# TOP_MOS_HF.net
KiCad netlist of a schematic drawn in Altium Designer
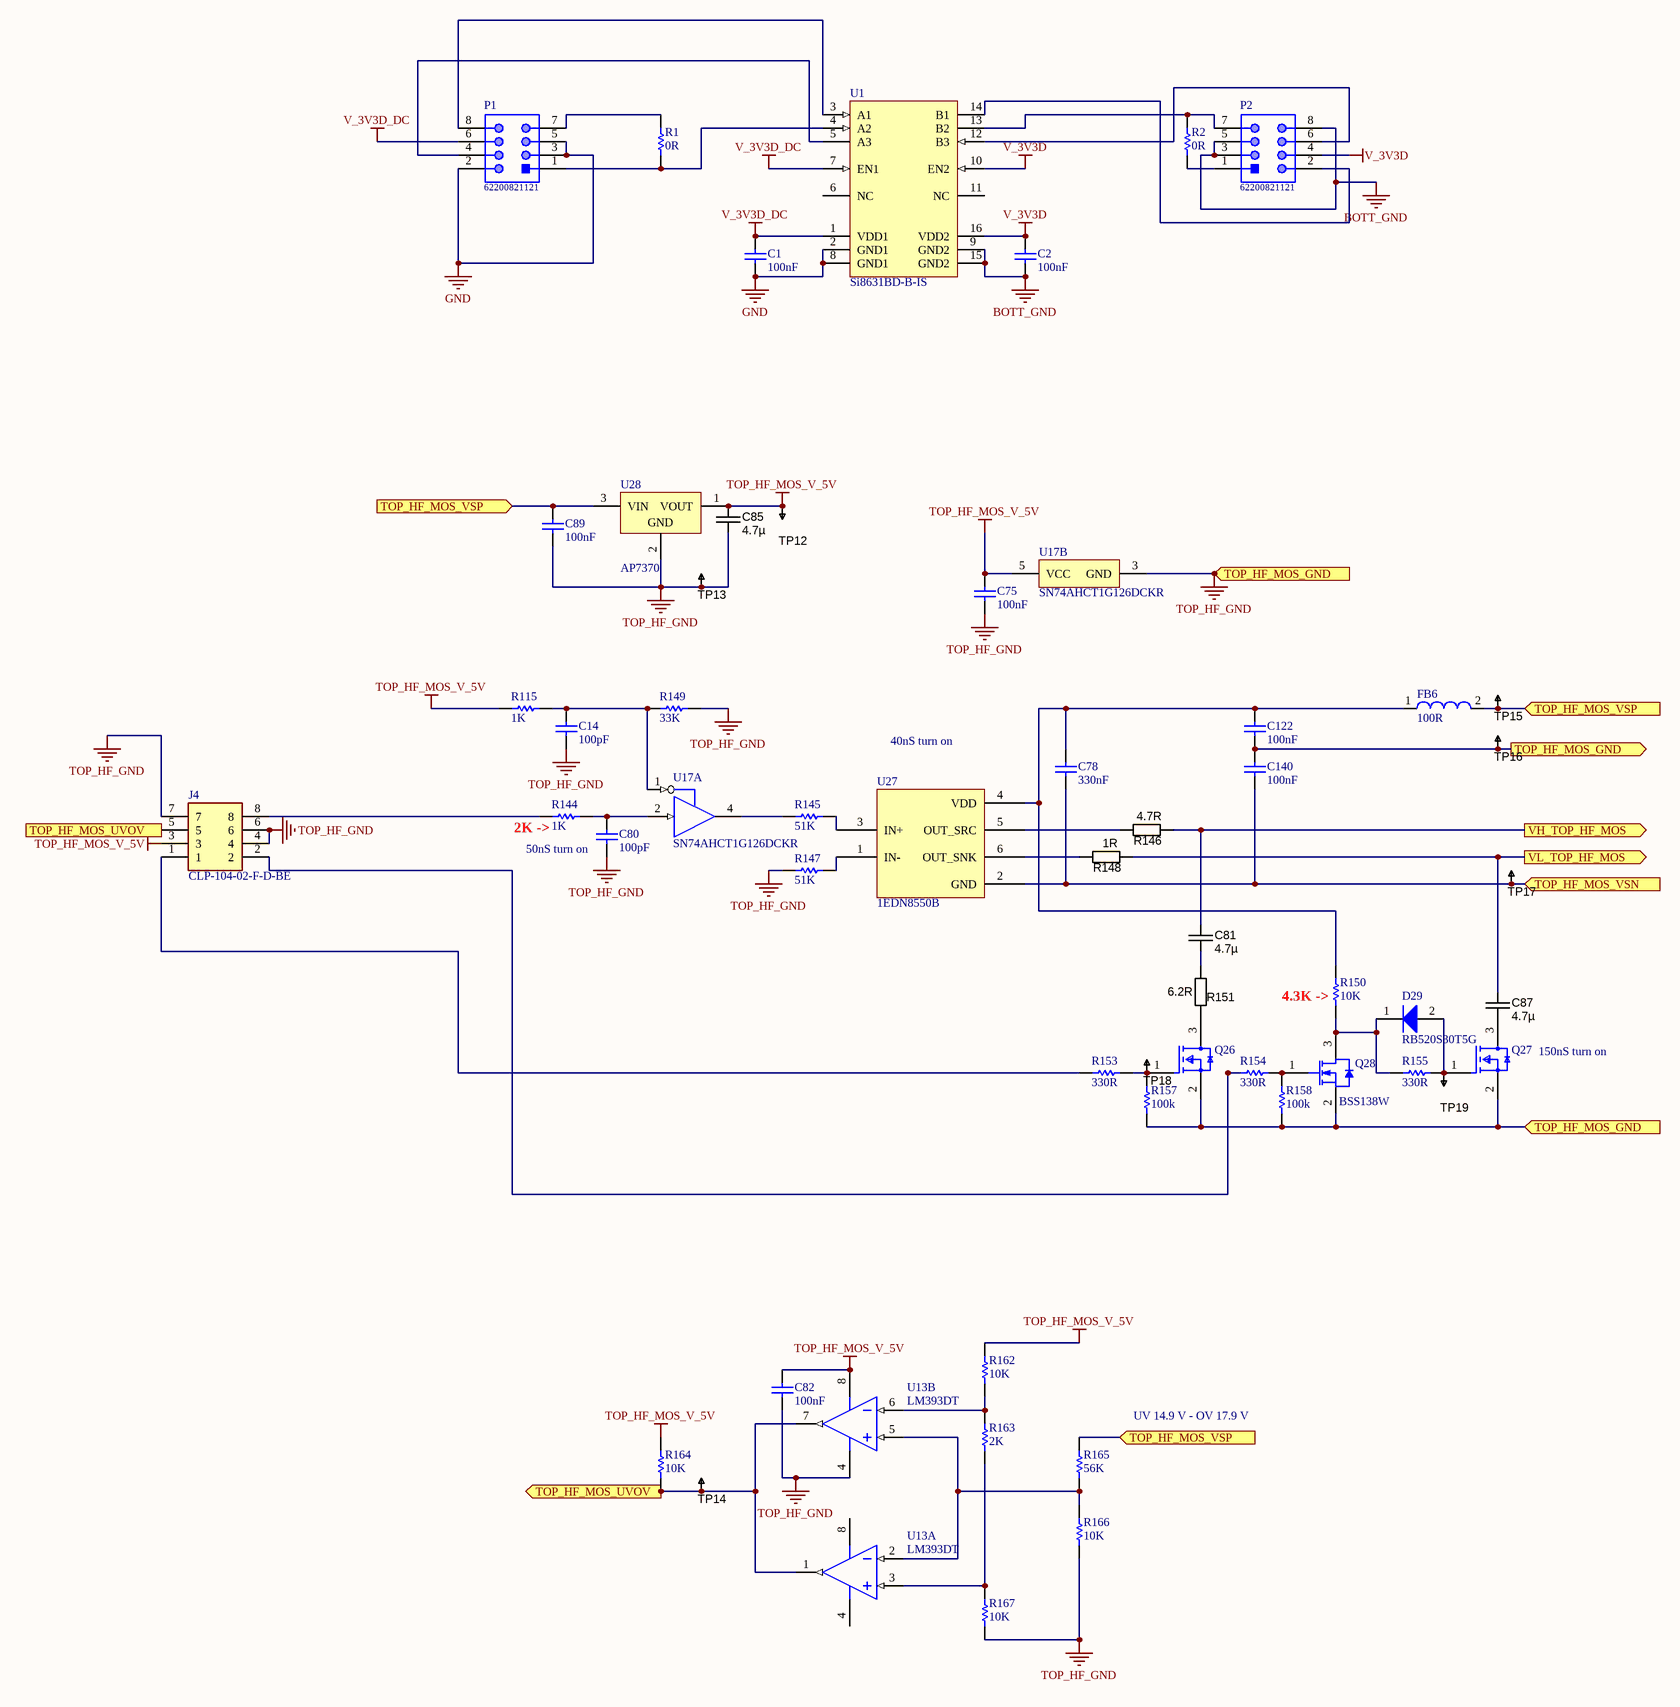
[diagram p0: TOP_MOS_HF.SchDoc]

(export (version "E")
  (design (tool "Eeschema 10.0.6"))
  (components
    (comp (ref "C1")
      (value "100nF")
      (footprint "SAMS-C0603-2_N")
      (description "Cap Ceramic 0.1uF 50VDC X7R 10% SMD 0603 Paper T/R")
      (fields
        (field (name "MANUFACTURER") "Samsung Electro-Mechanics")
        (field (name "MANUFACTURER PART NUMBER") "CL10B104KB8NNNC")
      )
      (libsource (lib "Altium Content Vault") (part "CAP-NP-2"))
    )
    (comp (ref "C2")
      (value "100nF")
      (footprint "SAMS-C0603-2_N")
      (description "Cap Ceramic 0.1uF 50VDC X7R 10% SMD 0603 Paper T/R")
      (fields
        (field (name "MANUFACTURER") "Samsung Electro-Mechanics")
        (field (name "MANUFACTURER PART NUMBER") "CL10B104KB8NNNC")
      )
      (libsource (lib "Altium Content Vault") (part "CAP-NP-2"))
    )
    (comp (ref "C14")
      (value "100pF")
      (footprint "CAPC1005X55X25NL05T10")
      (description "C0G ±5% 50V 100pF 0402 Multilayer Ceramic Capacitors MLCC - SMD/SMT ROHS")
      (fields (field (name "PART NUMBER") "GRM1555C1H100JA01D") (field (name "MANUFACTURER") "Murata"))
      (libsource (lib "DCDC") (part "CMP-2008-04245-1"))
    )
    (comp (ref "C75")
      (value "100nF")
      (footprint "CAPC1608X90X35NL10T15")
      (description "X7R 100nF ±10% 50V 0603 Multilayer Ceramic Capacitors MLCC - SMD/SMT ROHS")
      (fields (field (name "PART NUMBER") "GCM188R72A104KA64D") (field (name "MANUFACTURER") "Murata"))
      (libsource (lib "DCDC") (part "CAP"))
    )
    (comp (ref "C78")
      (value "330nF")
      (footprint "CAPC2013X135X45NL10T25")
      (description "X7R ±10% 50V 330nF 0805 Multilayer Ceramic Capacitors MLCC - SMD/SMT ROHS")
      (fields (field (name "VOLTAGE") "50V") (field (name "TOLERANCE") "10%"))
      (libsource (lib "Altium Content Vault") (part "CAP-NP-2"))
    )
    (comp (ref "C80")
      (value "100pF")
      (footprint "CAPC1005X55X25NL05T10")
      (description "C0G ±5% 50V 100pF 0402 Multilayer Ceramic Capacitors MLCC - SMD/SMT ROHS")
      (fields (field (name "PART NUMBER") "GRM1555C1H100JA01D") (field (name "MANUFACTURER") "Murata"))
      (libsource (lib "DCDC") (part "CMP-2008-04245-1"))
    )
    (comp (ref "C81")
      (value "4.7µ")
      (footprint "CAPC2012X135N")
      (description "X5R 25V ±10% 4.7uF 0805 Multilayer Ceramic Capacitors MLCC - SMD/SMT ROHS")
      (fields (field (name "TOLERANCE") "±10%") (field (name "JLCPCB PART #") "C1779"))
      (libsource (lib "PBL - Capacitors") (part "CAPC_1u_0805_X7R_16V_10%"))
    )
    (comp (ref "C82")
      (value "100nF")
      (footprint "CAPC1608X90X35NL10T15")
      (description "X7R 100nF ±10% 50V 0603 Multilayer Ceramic Capacitors MLCC - SMD/SMT ROHS")
      (fields (field (name "PART NUMBER") "GCM188R72A104KA64D") (field (name "MANUFACTURER") "Murata"))
      (libsource (lib "DCDC") (part "CAP"))
    )
    (comp (ref "C85")
      (value "4.7µ")
      (footprint "CAPC2012X135N")
      (description "X5R 25V ±10% 4.7uF 0805 Multilayer Ceramic Capacitors MLCC - SMD/SMT ROHS")
      (fields (field (name "TOLERANCE") "±10%") (field (name "JLCPCB PART #") "C1779"))
      (libsource (lib "PBL - Capacitors") (part "CAPC_1u_0805_X7R_16V_10%"))
    )
    (comp (ref "C87")
      (value "4.7µ")
      (footprint "CAPC2012X135N")
      (description "X5R 25V ±10% 4.7uF 0805 Multilayer Ceramic Capacitors MLCC - SMD/SMT ROHS")
      (fields (field (name "TOLERANCE") "±10%") (field (name "JLCPCB PART #") "C1779"))
      (libsource (lib "PBL - Capacitors") (part "CAPC_1u_0805_X7R_16V_10%"))
    )
    (comp (ref "C89")
      (value "100nF")
      (footprint "CAPC1608X90X35NL10T15")
      (description "X7R 100nF ±10% 50V 0603 Multilayer Ceramic Capacitors MLCC - SMD/SMT ROHS")
      (fields (field (name "PART NUMBER") "GCM188R72A104KA64D") (field (name "MANUFACTURER") "Murata"))
      (libsource (lib "DCDC") (part "CAP"))
    )
    (comp (ref "C122")
      (value "100nF")
      (footprint "CAPC1608X90X35NL10T15")
      (description "X7R 100nF ±10% 50V 0603 Multilayer Ceramic Capacitors MLCC - SMD/SMT ROHS")
      (fields (field (name "PART NUMBER") "GCM188R72A104KA64D") (field (name "MANUFACTURER") "Murata"))
      (libsource (lib "DCDC") (part "CAP"))
    )
    (comp (ref "C140")
      (value "100nF")
      (footprint "CAPC1608X90X35NL10T15")
      (description "X7R 100nF ±10% 50V 0603 Multilayer Ceramic Capacitors MLCC - SMD/SMT ROHS")
      (fields (field (name "PART NUMBER") "GCM188R72A104KA64D") (field (name "MANUFACTURER") "Murata"))
      (libsource (lib "DCDC") (part "CAP"))
    )
    (comp (ref "D29")
      (value "RB520S30T5G")
      (footprint "ONSC-SOD-523-2-502-01_V")
      (description "Schottky Barrier Diode, 2-Pin SOD-523, Pb-Free, Tape and Reel")
      (fields (field (name "MANUFACTURER") "On Semiconductor"))
      (libsource (lib "Altium Content Vault") (part "ONSC-D-K1A2-2"))
    )
    (comp (ref "FB6")
      (value "100R")
      (footprint "SMD-0603")
      (description "SMD EMI Suppression Ferrite Bead WE-CBF, Z = 1500 Ohm")
      (libsource (lib "Altium Content Vault") (part "PAS-IND-INDUCTOR-2"))
    )
    (comp (ref "J4")
      (value "CLP-104-02-F-D-BE")
      (footprint "SamacSys:CLP-104-02-XXX-D-BE")
      (description "Connector")
      (fields (field (name "MOUSER PART NUMBER") "200-CLP10402FDBE"))
      (libsource (lib "*") (part "CLP-104-02-F-D-BE"))
    )
    (comp (ref "P1")
      (value "62200821121")
      (footprint "EDGE GOLDPIN 8P 1.27MM")
      (description "THT Vertical Pin Header WR-PHD, Pitch 1.27 mm, Dual Row, 8 pins")
      (fields (field (name "MANUFACTURER") "Wurth Elektronik") (field (name "PUBLISHER") "WurthElektronik"))
      (libsource (lib "") (part "WE-CN-2P-M-R8_1"))
    )
    (comp (ref "P2")
      (value "62200821121")
      (footprint "EDGE GOLDPIN 8P 1.27MM")
      (description "THT Vertical Pin Header WR-PHD, Pitch 1.27 mm, Dual Row, 8 pins")
      (fields (field (name "MANUFACTURER") "Wurth Elektronik") (field (name "PUBLISHER") "WurthElektronik"))
      (libsource (lib "SamacSys") (part "WE-CN-2P-M-R8"))
    )
    (comp (ref "Q26")
      (value "DMN3067LW-7")
      (footprint "FP-SOT323-IPC_C")
      (description "MOSFET N-CH 60V 115MA SOT323")
      (libsource (lib "Altium Content Vault") (part "381a366367e4312d0f7d2747150cb42"))
    )
    (comp (ref "Q27")
      (value "DMN3067LW-7")
      (footprint "FP-SOT323-IPC_C")
      (description "MOSFET N-CH 60V 115MA SOT323")
      (libsource (lib "Altium Content Vault") (part "381a366367e4312d0f7d2747150cb42"))
    )
    (comp (ref "Q28")
      (value "BSS138W")
      (footprint "NXP-SOT323_M")
      (description "N-Channel Trench MOSFET, 60 V, 0.32 A, -55 to 150 degC, 3-Pin SOT323, Tape and Reel")
      (fields (field (name "PARTNUMBER") "BSS138PW,115") (field (name "MANUFACTURER") "NXP Semiconductors"))
      (libsource (lib "Altium Content Vault") (part "NXP-NMOS-GSD-3_B"))
    )
    (comp (ref "R1")
      (value "0R")
      (footprint "RESC1608X55X25ML10T15")
      (description "Chip Resistor, 0 Ohm, +/- 5%, 0.1 W, -55 to 155 degC, 0603 (1608 Metric), RoHS, Tape and Reel")
      (fields (field (name "TOLERANCE") "5%") (field (name "MANUFACTURER") "Yageo"))
      (libsource (lib "Altium Content Vault") (part "RES-2"))
    )
    (comp (ref "R2")
      (value "0R")
      (footprint "RESC1608X55X25ML10T15")
      (description "Chip Resistor, 0 Ohm, +/- 5%, 0.1 W, -55 to 155 degC, 0603 (1608 Metric), RoHS, Tape and Reel")
      (fields (field (name "TOLERANCE") "5%") (field (name "MANUFACTURER") "Yageo"))
      (libsource (lib "Altium Content Vault") (part "RES-2"))
    )
    (comp (ref "R115")
      (value "1K")
      (footprint "RESC1005X40X25NL05T10")
      (description "±1% 1/16W ±100ppm/℃ 1kΩ 0402 Chip Resistor - Surface Mount ROHS")
      (fields (field (name "PART NUMBER") "RC0402FR-071KL") (field (name "MANUFACTURER") "Yageo / Phycomp"))
      (libsource (lib "DCDC") (part "CMP-2002-07472-1"))
    )
    (comp (ref "R144")
      (value "1K")
      (footprint "RESC1005X40X25NL05T10")
      (description "±1% 1/16W ±100ppm/℃ 1kΩ 0402 Chip Resistor - Surface Mount ROHS")
      (fields (field (name "PART NUMBER") "RC0402FR-071KL") (field (name "MANUFACTURER") "Yageo / Phycomp"))
      (libsource (lib "DCDC") (part "CMP-2002-07472-1"))
    )
    (comp (ref "R145")
      (value "51K")
      (footprint "RESC1005X40X25ML05T05")
      (fields
        (field (name "PART NUMBER") "ERJ2RKF3302X")
        (field (name "MANUFACTURER") "Panasonic")
        (field (name "MANUFACTURER PART NUMBER") "ERJ-2RKF3302X")
      )
      (libsource (lib "Altium Content Vault") (part "RES"))
    )
    (comp (ref "R146")
      (value "4.7R")
      (footprint "RESC2012X70N")
      (description "4.7Ω ±1% ±400ppm/℃ 0.125W 0805 Chip Resistor - Surface Mount ROHS")
      (fields (field (name "JLCPCB PART #") "C17675"))
      (libsource (lib "PBL - Resistors") (part "RES_EMPTY_0805"))
    )
    (comp (ref "R147")
      (value "51K")
      (footprint "RESC1005X40X25ML05T05")
      (fields
        (field (name "PART NUMBER") "ERJ2RKF3302X")
        (field (name "MANUFACTURER") "Panasonic")
        (field (name "MANUFACTURER PART NUMBER") "ERJ-2RKF3302X")
      )
      (libsource (lib "Altium Content Vault") (part "RES"))
    )
    (comp (ref "R148")
      (value "1R")
      (footprint "RESC2012X70N")
      (description "±1% 1Ω ±400ppm/℃ 0.125W 0805 Chip Resistor - Surface Mount ROHS")
      (fields (field (name "JLCPCB PART #") "C25271"))
      (libsource (lib "PBL - Resistors") (part "RES_EMPTY_0805"))
    )
    (comp (ref "R149")
      (value "33K")
      (footprint "RESC1005X40X25ML05T05")
      (fields
        (field (name "PART NUMBER") "ERJ2RKF3302X")
        (field (name "MANUFACTURER") "Panasonic")
        (field (name "MANUFACTURER PART NUMBER") "ERJ-2RKF3302X")
      )
      (libsource (lib "DCDC") (part "RES"))
    )
    (comp (ref "R150")
      (value "10K")
      (footprint "RESC1609X55X30NL15T15")
      (description "±1% ±100ppm/℃ 10kΩ 0.1W 0603 Chip Resistor - Surface Mount ROHS")
      (fields (field (name "TOLERANCE") "1%") (field (name "MANUFACTURER") "Panasonic"))
      (libsource (lib "Altium Content Vault") (part "RES-2"))
    )
    (comp (ref "R151")
      (value "6.2R")
      (footprint "RESC2012X70N")
      (description "Resistor, 0805 SMD, Empty footprint")
      (libsource (lib "") (part "RES_EMPTY_0805_1"))
    )
    (comp (ref "R153")
      (value "330R")
      (footprint "RESC1608X55X25NL10T15")
      (description "±1% 330Ω ±100ppm/℃ 0.1W 0603 Chip Resistor - Surface Mount ROHS")
      (fields (field (name "TOLERANCE") "10%") (field (name "JLCPCB PART #") "C23138"))
      (libsource (lib "Altium Content Vault") (part "RES-2"))
    )
    (comp (ref "R154")
      (value "330R")
      (footprint "RESC1608X55X25NL10T15")
      (description "±1% 330Ω ±100ppm/℃ 0.1W 0603 Chip Resistor - Surface Mount ROHS")
      (fields (field (name "TOLERANCE") "10%") (field (name "JLCPCB PART #") "C23138"))
      (libsource (lib "Altium Content Vault") (part "RES-2"))
    )
    (comp (ref "R155")
      (value "330R")
      (footprint "RESC1608X55X25NL10T15")
      (description "±1% 330Ω ±100ppm/℃ 0.1W 0603 Chip Resistor - Surface Mount ROHS")
      (fields (field (name "TOLERANCE") "10%") (field (name "JLCPCB PART #") "C23138"))
      (libsource (lib "Altium Content Vault") (part "RES-2"))
    )
    (comp (ref "R157")
      (value "100k")
      (footprint "RESC1608X55X30NL15T15")
      (description "±1% 100kΩ ±100ppm/℃ 0.1W 0603 Chip Resistor - Surface Mount ROHS")
      (fields (field (name "PART NUMBER") "ERJ-3EKF1003V") (field (name "MANUFACTURER") "Panasonic"))
      (libsource (lib "Altium Content Vault") (part "RES"))
    )
    (comp (ref "R158")
      (value "100k")
      (footprint "RESC1608X55X30NL15T15")
      (description "±1% 100kΩ ±100ppm/℃ 0.1W 0603 Chip Resistor - Surface Mount ROHS")
      (fields (field (name "PART NUMBER") "ERJ-3EKF1003V") (field (name "MANUFACTURER") "Panasonic"))
      (libsource (lib "Altium Content Vault") (part "RES"))
    )
    (comp (ref "R162")
      (value "10K")
      (footprint "RESC1609X55X30NL15T15")
      (description "±1% ±100ppm/℃ 10kΩ 0.1W 0603 Chip Resistor - Surface Mount ROHS")
      (fields (field (name "TOLERANCE") "1%") (field (name "MANUFACTURER") "Panasonic"))
      (libsource (lib "DCDC") (part "RES-2"))
    )
    (comp (ref "R163")
      (value "2K")
      (footprint "RESC1609X55X30NL15T15")
      (description "±1% 2kΩ ±100ppm/℃ 0.1W 0603 Chip Resistor - Surface Mount ROHS")
      (fields (field (name "TOLERANCE") "1%") (field (name "MANUFACTURER") "Panasonic"))
      (libsource (lib "DCDC") (part "RES-2"))
    )
    (comp (ref "R164")
      (value "10K")
      (footprint "RESC1609X55X30NL15T15")
      (description "±1% ±100ppm/℃ 10kΩ 0.1W 0603 Chip Resistor - Surface Mount ROHS")
      (fields (field (name "TOLERANCE") "1%") (field (name "MANUFACTURER") "Panasonic"))
      (libsource (lib "DCDC") (part "RES-2"))
    )
    (comp (ref "R165")
      (value "56K")
      (footprint "RESC1609X55X30NL15T15")
      (description "±1% ±100ppm/℃ 56kΩ 0.1W 0603 Chip Resistor - Surface Mount ROHS")
      (fields (field (name "TOLERANCE") "1%") (field (name "MANUFACTURER") "Panasonic"))
      (libsource (lib "DCDC") (part "RES-2"))
    )
    (comp (ref "R166")
      (value "10K")
      (footprint "RESC1609X55X30NL15T15")
      (description "±1% ±100ppm/℃ 10kΩ 0.1W 0603 Chip Resistor - Surface Mount ROHS")
      (fields (field (name "TOLERANCE") "1%") (field (name "MANUFACTURER") "Panasonic"))
      (libsource (lib "DCDC") (part "RES-2"))
    )
    (comp (ref "R167")
      (value "10K")
      (footprint "RESC1609X55X30NL15T15")
      (description "±1% ±100ppm/℃ 10kΩ 0.1W 0603 Chip Resistor - Surface Mount ROHS")
      (fields (field (name "TOLERANCE") "1%") (field (name "MANUFACTURER") "Panasonic"))
      (libsource (lib "DCDC") (part "RES-2"))
    )
    (comp (ref "TP12")
      (value "TESTPOINT")
      (footprint "TP-R60")
      (description "SMD test pin")
      (libsource (lib "PBL - Test Points") (part "TESTPOINT"))
    )
    (comp (ref "TP13")
      (value "TESTPOINT")
      (footprint "TP-R60")
      (description "SMD test pin")
      (libsource (lib "PBL - Test Points") (part "TESTPOINT"))
    )
    (comp (ref "TP14")
      (value "TESTPOINT")
      (footprint "TP-R60")
      (description "SMD test pin")
      (libsource (lib "PBL - Test Points") (part "TESTPOINT"))
    )
    (comp (ref "TP15")
      (value "TESTPOINT")
      (footprint "TP-R60")
      (description "SMD test pin")
      (libsource (lib "PBL - Test Points") (part "TESTPOINT"))
    )
    (comp (ref "TP16")
      (value "TESTPOINT")
      (footprint "TP-R60")
      (description "SMD test pin")
      (libsource (lib "PBL - Test Points") (part "TESTPOINT"))
    )
    (comp (ref "TP17")
      (value "TESTPOINT")
      (footprint "TP-R60")
      (description "SMD test pin")
      (libsource (lib "PBL - Test Points") (part "TESTPOINT"))
    )
    (comp (ref "TP18")
      (value "TESTPOINT")
      (footprint "TP-R60")
      (description "SMD test pin")
      (libsource (lib "PBL - Test Points") (part "TESTPOINT"))
    )
    (comp (ref "TP19")
      (value "TESTPOINT")
      (footprint "TP-R60")
      (description "SMD test pin")
      (libsource (lib "PBL - Test Points") (part "TESTPOINT"))
    )
    (comp (ref "U1")
      (value "Si8631BD-B-IS")
      (footprint "SLAB-SOIC-16-WB_N")
      (fields (field (name "MANUFACTURER") "Silicon Labs"))
      (libsource (lib "Altium Content Vault") (part "SLAB-Si8X31BB-SOIC-16-XB-16X"))
    )
    (comp (ref "U13")
      (value "LM393DT")
      (footprint "SOT65P280X110-8N")
      (description "Low-Power, Dual-Voltage Comparator, 2 to 36 V, 0 to 70 degC, 8-Pin SOIC (SO), RoHS, Tape and Reel")
      (fields (field (name "MANUFACTURER") "STMicroelectronics"))
      (libsource (lib "SamacSys") (part "STM-LM393-SO8"))
    )
    (comp (ref "U17")
      (value "SN74AHCT1G126DCKR")
      (footprint "DCK0005A_L")
      (description "Single Bus Buffer Gate With 3-State Output, DCK0005A, LARGE T&R")
      (fields
        (field (name "MANUFACTURER") "Texas Instruments")
        (field (name "GENERIC PART NUMBER") "SN74AHCT1G126")
      )
      (libsource (lib "Altium Content Vault") (part "TI-SN74XXXXXX126-5"))
    )
    (comp (ref "U27")
      (value "1EDN8550B")
      (footprint "SOT23-6")
      (description "Single-channel EiceDRIVER™ with true  differential inputs")
      (libsource (lib "1EDN8550B") (part "1EDN8550B"))
    )
    (comp (ref "U28")
      (value "AP7370")
      (footprint "SOT-89_L")
      (libsource (lib "Altium Content Vault") (part "PM-REG-7805-SIL3"))
    )
  )
  (nets
    (net (code "1") (name "/TOP_HF_MOS_UVOV") (class "Default")
      (node (ref "J4") (pin "5") (pinfunction "5_5") (pintype "passive"))
      (node (ref "R164") (pin "2") (pinfunction "2_2") (pintype "passive"))
      (node (ref "TP14") (pin "1") (pintype "passive"))
      (node (ref "U13") (pin "1") (pinfunction "OUT1_1") (pintype "output"))
      (node (ref "U13") (pin "7") (pinfunction "OUT2_7") (pintype "output"))
    )
    (net (code "2") (name "/TOP_HF_MOS_VSN") (class "Default")
      (node (ref "C140") (pin "1") (pinfunction "1_1") (pintype "passive"))
      (node (ref "C78") (pin "1") (pinfunction "1_1") (pintype "passive"))
      (node (ref "TP17") (pin "1") (pintype "passive"))
      (node (ref "U27") (pin "2") (pinfunction "GND_2") (pintype "passive"))
    )
    (net (code "3") (name "/TOP_HF_MOS_VSP") (class "Default")
      (node (ref "C89") (pin "2") (pinfunction "2_2") (pintype "passive"))
      (node (ref "FB6") (pin "2") (pinfunction "2_2") (pintype "passive"))
      (node (ref "R165") (pin "1") (pinfunction "1_1") (pintype "passive"))
      (node (ref "TP15") (pin "1") (pintype "passive"))
      (node (ref "U28") (pin "3") (pinfunction "VIN_3") (pintype "power_in"))
    )
    (net (code "4") (name "/VH_TOP_HF_MOS") (class "Default")
      (node (ref "C81") (pin "1") (pintype "passive"))
      (node (ref "R146") (pin "2") (pinfunction "2_2") (pintype "passive"))
    )
    (net (code "5") (name "/VL_TOP_HF_MOS") (class "Default")
      (node (ref "C87") (pin "1") (pintype "passive"))
      (node (ref "R148") (pin "2") (pinfunction "2_2") (pintype "passive"))
    )
    (net (code "6") (name "BOTT_GND") (class "Default")
      (node (ref "C2") (pin "2") (pinfunction "2_2") (pintype "passive"))
      (node (ref "P2") (pin "3") (pinfunction "3_3") (pintype "passive"))
      (node (ref "P2") (pin "5") (pinfunction "5_5") (pintype "passive"))
      (node (ref "P2") (pin "8") (pinfunction "8_8") (pintype "passive"))
      (node (ref "U1") (pin "15") (pinfunction "GND2_15") (pintype "power_in"))
      (node (ref "U1") (pin "9") (pinfunction "GND2_9") (pintype "power_in"))
    )
    (net (code "7") (name "GND") (class "Default")
      (node (ref "C1") (pin "2") (pinfunction "2_2") (pintype "passive"))
      (node (ref "P1") (pin "2") (pinfunction "2_2") (pintype "passive"))
      (node (ref "P1") (pin "3") (pinfunction "3_3") (pintype "passive"))
      (node (ref "P1") (pin "5") (pinfunction "5_5") (pintype "passive"))
      (node (ref "U1") (pin "2") (pinfunction "GND1_2") (pintype "power_in"))
      (node (ref "U1") (pin "8") (pinfunction "GND1_8") (pintype "power_in"))
    )
    (net (code "8") (name "Net-(C81-Pad2)") (class "Default")
      (node (ref "C81") (pin "2") (pintype "passive"))
      (node (ref "R151") (pin "2") (pinfunction "2_2") (pintype "passive"))
    )
    (net (code "9") (name "Net-(D29-A)") (class "Default")
      (node (ref "D29") (pin "2") (pinfunction "A_2") (pintype "passive"))
      (node (ref "Q27") (pin "1") (pinfunction "G_1") (pintype "passive"))
      (node (ref "R155") (pin "2") (pinfunction "2_2") (pintype "passive"))
      (node (ref "TP19") (pin "1") (pintype "passive"))
    )
    (net (code "10") (name "Net-(D29-K)") (class "Default")
      (node (ref "D29") (pin "1") (pinfunction "K_1") (pintype "passive"))
      (node (ref "Q28") (pin "3") (pinfunction "D_3") (pintype "passive"))
      (node (ref "R150") (pin "2") (pinfunction "2_2") (pintype "passive"))
      (node (ref "R155") (pin "1") (pinfunction "1_1") (pintype "passive"))
    )
    (net (code "11") (name "Net-(J4-Pad1)") (class "Default")
      (node (ref "J4") (pin "1") (pinfunction "1_1") (pintype "passive"))
      (node (ref "R153") (pin "1") (pinfunction "1_1") (pintype "passive"))
    )
    (net (code "12") (name "Net-(J4-Pad2)") (class "Default")
      (node (ref "J4") (pin "2") (pinfunction "2_2") (pintype "passive"))
      (node (ref "R154") (pin "1") (pinfunction "1_1") (pintype "passive"))
    )
    (net (code "13") (name "Net-(J4-Pad8)") (class "Default")
      (node (ref "J4") (pin "8") (pinfunction "8_8") (pintype "passive"))
      (node (ref "R144") (pin "1") (pinfunction "1_1") (pintype "passive"))
    )
    (net (code "14") (name "Net-(P1-Pad7)") (class "Default")
      (node (ref "P1") (pin "7") (pinfunction "7_7") (pintype "passive"))
      (node (ref "R1") (pin "1") (pinfunction "1_1") (pintype "passive"))
    )
    (net (code "15") (name "Net-(P2-Pad1)") (class "Default")
      (node (ref "P2") (pin "1") (pinfunction "1_1") (pintype "passive"))
      (node (ref "R2") (pin "2") (pinfunction "2_2") (pintype "passive"))
    )
    (net (code "16") (name "Net-(Q26-D)") (class "Default")
      (node (ref "Q26") (pin "3") (pinfunction "D_3") (pintype "passive"))
      (node (ref "R151") (pin "1") (pinfunction "1_1") (pintype "passive"))
    )
    (net (code "17") (name "Net-(Q26-G)") (class "Default")
      (node (ref "Q26") (pin "1") (pinfunction "G_1") (pintype "passive"))
      (node (ref "R153") (pin "2") (pinfunction "2_2") (pintype "passive"))
      (node (ref "R157") (pin "2") (pinfunction "2_2") (pintype "passive"))
      (node (ref "TP18") (pin "1") (pintype "passive"))
    )
    (net (code "18") (name "Net-(Q27-D)") (class "Default")
      (node (ref "C87") (pin "2") (pintype "passive"))
      (node (ref "Q27") (pin "3") (pinfunction "D_3") (pintype "passive"))
    )
    (net (code "19") (name "Net-(Q28-G)") (class "Default")
      (node (ref "Q28") (pin "1") (pinfunction "G_1") (pintype "passive"))
      (node (ref "R154") (pin "2") (pinfunction "2_2") (pintype "passive"))
      (node (ref "R158") (pin "2") (pinfunction "2_2") (pintype "passive"))
    )
    (net (code "20") (name "Net-(U1-A1)") (class "Default")
      (node (ref "P1") (pin "8") (pinfunction "8_8") (pintype "passive"))
      (node (ref "U1") (pin "3") (pinfunction "A1_3") (pintype "input"))
    )
    (net (code "21") (name "Net-(U1-A2)") (class "Default")
      (node (ref "P1") (pin "1") (pinfunction "1_1") (pintype "passive"))
      (node (ref "R1") (pin "2") (pinfunction "2_2") (pintype "passive"))
      (node (ref "U1") (pin "4") (pinfunction "A2_4") (pintype "input"))
    )
    (net (code "22") (name "Net-(U1-A3)") (class "Default")
      (node (ref "P1") (pin "4") (pinfunction "4_4") (pintype "passive"))
      (node (ref "U1") (pin "5") (pinfunction "A3_5") (pintype "tri_state"))
    )
    (net (code "23") (name "Net-(U1-B1)") (class "Default")
      (node (ref "P2") (pin "2") (pinfunction "2_2") (pintype "passive"))
      (node (ref "U1") (pin "14") (pinfunction "B1_14") (pintype "tri_state"))
    )
    (net (code "24") (name "Net-(U1-B2)") (class "Default")
      (node (ref "P2") (pin "7") (pinfunction "7_7") (pintype "passive"))
      (node (ref "R2") (pin "1") (pinfunction "1_1") (pintype "passive"))
      (node (ref "U1") (pin "13") (pinfunction "B2_13") (pintype "tri_state"))
    )
    (net (code "25") (name "Net-(U1-B3)") (class "Default")
      (node (ref "P2") (pin "6") (pinfunction "6_6") (pintype "passive"))
      (node (ref "U1") (pin "12") (pinfunction "B3_12") (pintype "input"))
    )
    (net (code "26") (name "Net-(U13A-IN1+)") (class "Default")
      (node (ref "R163") (pin "2") (pinfunction "2_2") (pintype "passive"))
      (node (ref "R167") (pin "1") (pinfunction "1_1") (pintype "passive"))
      (node (ref "U13") (pin "3") (pinfunction "IN1+_3") (pintype "input"))
    )
    (net (code "27") (name "Net-(U13A-IN1-)") (class "Default")
      (node (ref "R165") (pin "2") (pinfunction "2_2") (pintype "passive"))
      (node (ref "R166") (pin "1") (pinfunction "1_1") (pintype "passive"))
      (node (ref "U13") (pin "2") (pinfunction "IN1-_2") (pintype "input"))
      (node (ref "U13") (pin "5") (pinfunction "IN2+_5") (pintype "input"))
    )
    (net (code "28") (name "Net-(U13B-IN2-)") (class "Default")
      (node (ref "R162") (pin "2") (pinfunction "2_2") (pintype "passive"))
      (node (ref "R163") (pin "1") (pinfunction "1_1") (pintype "passive"))
      (node (ref "U13") (pin "6") (pinfunction "IN2-_6") (pintype "input"))
    )
    (net (code "29") (name "Net-(U17A-A)") (class "Default")
      (node (ref "C80") (pin "2") (pinfunction "2_2") (pintype "passive"))
      (node (ref "R144") (pin "2") (pinfunction "2_2") (pintype "passive"))
      (node (ref "U17") (pin "2") (pinfunction "A_2") (pintype "input"))
    )
    (net (code "30") (name "Net-(U17A-OE)") (class "Default")
      (node (ref "C14") (pin "2") (pinfunction "2_2") (pintype "passive"))
      (node (ref "R115") (pin "2") (pinfunction "2_2") (pintype "passive"))
      (node (ref "R149") (pin "1") (pinfunction "1_1") (pintype "passive"))
      (node (ref "U17") (pin "1") (pinfunction "OE_1") (pintype "input"))
    )
    (net (code "31") (name "Net-(U17A-Y)") (class "Default")
      (node (ref "R145") (pin "1") (pinfunction "1_1") (pintype "passive"))
      (node (ref "U17") (pin "4") (pinfunction "Y_4") (pintype "tri_state"))
    )
    (net (code "32") (name "Net-(U27-IN+)") (class "Default")
      (node (ref "R145") (pin "2") (pinfunction "2_2") (pintype "passive"))
      (node (ref "U27") (pin "3") (pinfunction "IN+_3") (pintype "passive"))
    )
    (net (code "33") (name "Net-(U27-IN-)") (class "Default")
      (node (ref "R147") (pin "2") (pinfunction "2_2") (pintype "passive"))
      (node (ref "U27") (pin "1") (pinfunction "IN-_1") (pintype "passive"))
    )
    (net (code "34") (name "Net-(U27-OUT_SNK)") (class "Default")
      (node (ref "R148") (pin "1") (pinfunction "1_1") (pintype "passive"))
      (node (ref "U27") (pin "6") (pinfunction "OUT_SNK_6") (pintype "passive"))
    )
    (net (code "35") (name "Net-(U27-OUT_SRC)") (class "Default")
      (node (ref "R146") (pin "1") (pinfunction "1_1") (pintype "passive"))
      (node (ref "U27") (pin "5") (pinfunction "OUT_SRC_5") (pintype "passive"))
    )
    (net (code "36") (name "Net-(U27-VDD)") (class "Default")
      (node (ref "C122") (pin "2") (pinfunction "2_2") (pintype "passive"))
      (node (ref "C78") (pin "2") (pinfunction "2_2") (pintype "passive"))
      (node (ref "FB6") (pin "1") (pinfunction "1_1") (pintype "passive"))
      (node (ref "R150") (pin "1") (pinfunction "1_1") (pintype "passive"))
      (node (ref "U27") (pin "4") (pinfunction "VDD_4") (pintype "passive"))
    )
    (net (code "37") (name "TOP_HF_GND") (class "Default")
      (node (ref "C122") (pin "1") (pinfunction "1_1") (pintype "passive"))
      (node (ref "C14") (pin "1") (pinfunction "1_1") (pintype "passive"))
      (node (ref "C140") (pin "2") (pinfunction "2_2") (pintype "passive"))
      (node (ref "C75") (pin "1") (pinfunction "1_1") (pintype "passive"))
      (node (ref "C80") (pin "1") (pinfunction "1_1") (pintype "passive"))
      (node (ref "C82") (pin "1") (pinfunction "1_1") (pintype "passive"))
      (node (ref "C85") (pin "2") (pintype "passive"))
      (node (ref "C89") (pin "1") (pinfunction "1_1") (pintype "passive"))
      (node (ref "J4") (pin "4") (pinfunction "4_4") (pintype "passive"))
      (node (ref "J4") (pin "6") (pinfunction "6_6") (pintype "passive"))
      (node (ref "J4") (pin "7") (pinfunction "7_7") (pintype "passive"))
      (node (ref "Q26") (pin "2") (pinfunction "S_2") (pintype "passive"))
      (node (ref "Q27") (pin "2") (pinfunction "S_2") (pintype "passive"))
      (node (ref "Q28") (pin "2") (pinfunction "S_2") (pintype "passive"))
      (node (ref "R147") (pin "1") (pinfunction "1_1") (pintype "passive"))
      (node (ref "R149") (pin "2") (pinfunction "2_2") (pintype "passive"))
      (node (ref "R157") (pin "1") (pinfunction "1_1") (pintype "passive"))
      (node (ref "R158") (pin "1") (pinfunction "1_1") (pintype "passive"))
      (node (ref "R166") (pin "2") (pinfunction "2_2") (pintype "passive"))
      (node (ref "R167") (pin "2") (pinfunction "2_2") (pintype "passive"))
      (node (ref "TP13") (pin "1") (pintype "passive"))
      (node (ref "TP16") (pin "1") (pintype "passive"))
      (node (ref "U13") (pin "4") (pinfunction "VCC-_4") (pintype "power_in"))
      (node (ref "U17") (pin "3") (pinfunction "GND_3") (pintype "power_in"))
      (node (ref "U28") (pin "2") (pinfunction "GND_2") (pintype "power_in"))
    )
    (net (code "38") (name "TOP_HF_MOS_V_5V") (class "Default")
      (node (ref "C75") (pin "2") (pinfunction "2_2") (pintype "passive"))
      (node (ref "C82") (pin "2") (pinfunction "2_2") (pintype "passive"))
      (node (ref "C85") (pin "1") (pintype "passive"))
      (node (ref "J4") (pin "3") (pinfunction "3_3") (pintype "passive"))
      (node (ref "R115") (pin "1") (pinfunction "1_1") (pintype "passive"))
      (node (ref "R162") (pin "1") (pinfunction "1_1") (pintype "passive"))
      (node (ref "R164") (pin "1") (pinfunction "1_1") (pintype "passive"))
      (node (ref "TP12") (pin "1") (pintype "passive"))
      (node (ref "U13") (pin "8") (pinfunction "VCC+_8") (pintype "power_in"))
      (node (ref "U17") (pin "5") (pinfunction "VCC_5") (pintype "power_in"))
      (node (ref "U28") (pin "1") (pinfunction "VOUT_1") (pintype "power_in"))
    )
    (net (code "39") (name "V_3V3D") (class "Default")
      (node (ref "C2") (pin "1") (pinfunction "1_1") (pintype "passive"))
      (node (ref "P2") (pin "4") (pinfunction "4_4") (pintype "passive"))
      (node (ref "U1") (pin "10") (pinfunction "EN2_10") (pintype "input"))
      (node (ref "U1") (pin "16") (pinfunction "VDD2_16") (pintype "power_in"))
    )
    (net (code "40") (name "V_3V3D_DC") (class "Default")
      (node (ref "C1") (pin "1") (pinfunction "1_1") (pintype "passive"))
      (node (ref "P1") (pin "6") (pinfunction "6_6") (pintype "passive"))
      (node (ref "U1") (pin "1") (pinfunction "VDD1_1") (pintype "power_in"))
      (node (ref "U1") (pin "7") (pinfunction "EN1_7") (pintype "input"))
    )
    (net (code "41") (name "unconnected-(U1-NC-Pad6)") (class "Default")
      (node (ref "U1") (pin "6") (pinfunction "NC_6") (pintype "passive"))
    )
    (net (code "42") (name "unconnected-(U1-NC-Pad11)") (class "Default")
      (node (ref "U1") (pin "11") (pinfunction "NC_11") (pintype "passive"))
    )
    (net (code "43") (name "unconnected-(U13A-VCC+-Pad8)") (class "Default")
      (node (ref "U13") (pin "8") (pinfunction "VCC+_8") (pintype "power_in"))
    )
    (net (code "44") (name "unconnected-(U13A-VCC--Pad4)") (class "Default")
      (node (ref "U13") (pin "4") (pinfunction "VCC-_4") (pintype "power_in"))
    )
  )
)
